# bolid-outputs.net
KiCad netlist of a schematic drawn in Altium Designer
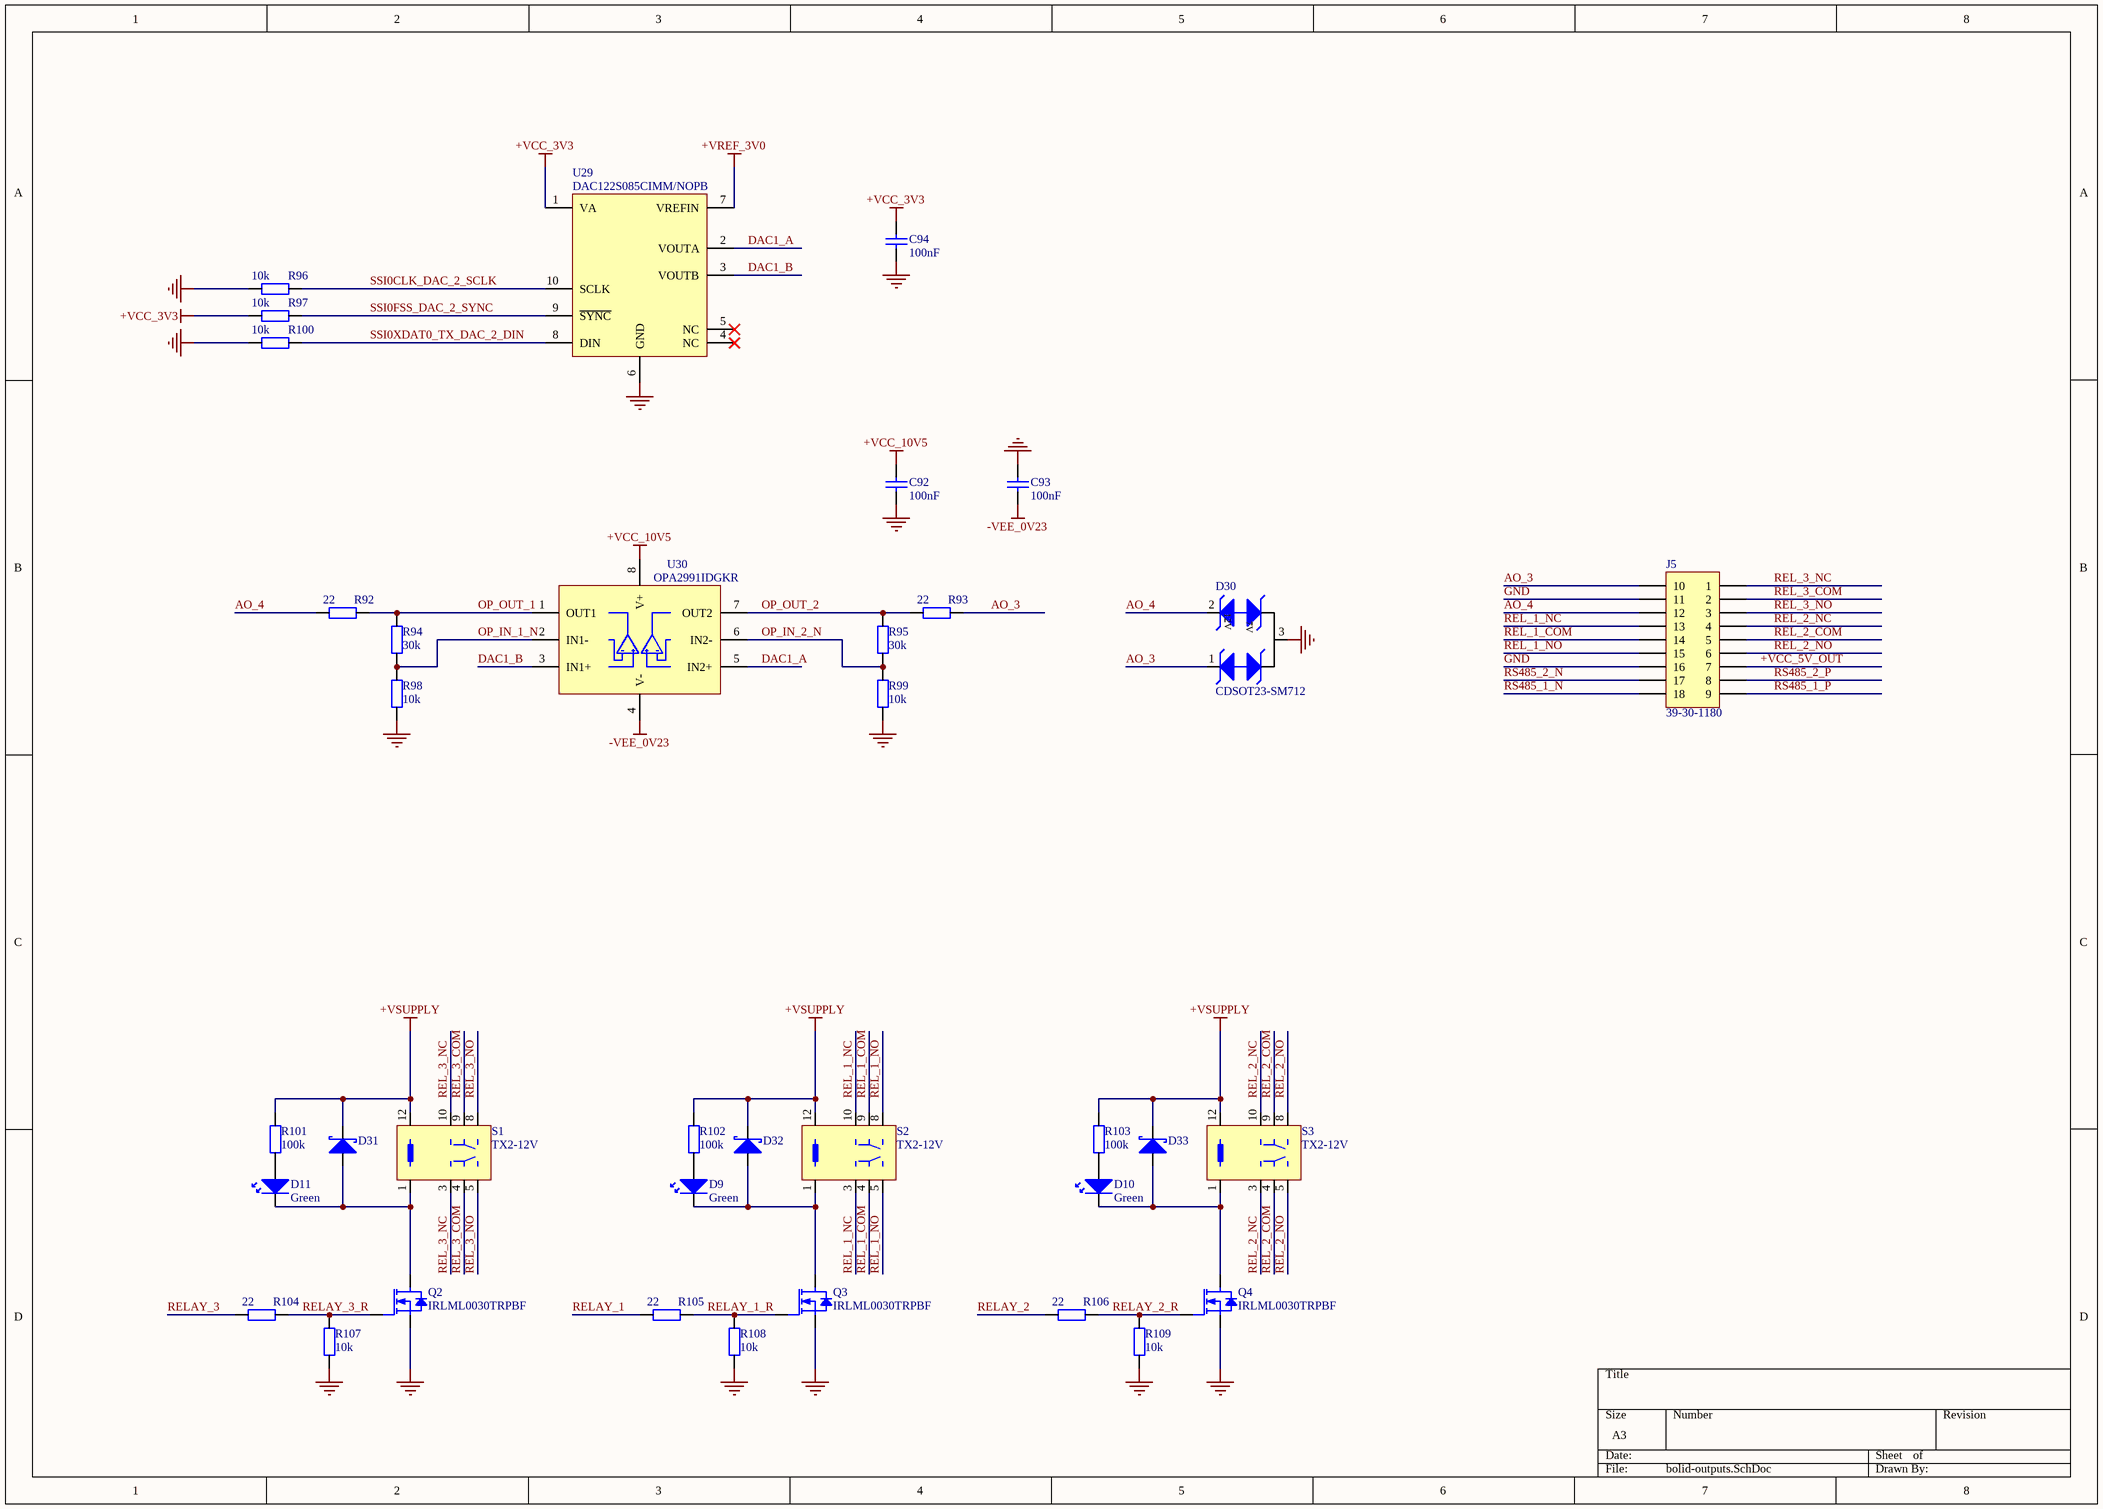
[diagram p0: bolid-outputs.SchDoc]

(export (version "E")
  (design (tool "Eeschema 10.0.6"))
  (components
    (comp (ref "C92")
      (value "GRM155R71H104KE14D")
      (footprint "C0402-CAPC100X50X55L22 - Tayio Yuden TDK")
      (description "MLCC 0402 (1005) 100nF 10% 50V X7R")
      (fields
        (field (name "MANUFACTURER") "Murata Electronics")
        (field (name "TOLERANCE") "10 %")
        (field (name "VALUE DISPLAYED") "100nF")
      )
      (libsource (lib "capacitors2") (part "GRM155R71H104KE14D"))
    )
    (comp (ref "C93")
      (value "GRM155R71H104KE14D")
      (footprint "C0402-CAPC100X50X55L22 - Tayio Yuden TDK")
      (description "MLCC 0402 (1005) 100nF 10% 50V X7R")
      (fields
        (field (name "MANUFACTURER") "Murata Electronics")
        (field (name "TOLERANCE") "10 %")
        (field (name "VALUE DISPLAYED") "100nF")
      )
      (libsource (lib "capacitors2") (part "GRM155R71H104KE14D"))
    )
    (comp (ref "C94")
      (value "GRM155R71H104KE14D")
      (footprint "C0402-CAPC100X50X55L22 - Tayio Yuden TDK")
      (description "MLCC 0402 (1005) 100nF 10% 50V X7R")
      (fields
        (field (name "MANUFACTURER") "Murata Electronics")
        (field (name "TOLERANCE") "10 %")
        (field (name "VALUE DISPLAYED") "100nF")
      )
      (libsource (lib "capacitors2") (part "GRM155R71H104KE14D"))
    )
    (comp (ref "D9")
      (value "150060GS75000")
      (footprint "D0603 DIONC166X84X36L42N Littelfuse")
      (description "LED 0603 (1608) Green")
      (fields (field (name "MANUFACTURER") "Wurth Elektronik") (field (name "ILLUMINATION COLOR") "Green"))
      (libsource (lib "semiconductors2") (part "150060GS75000"))
    )
    (comp (ref "D10")
      (value "150060GS75000")
      (footprint "D0603 DIONC166X84X36L42N Littelfuse")
      (description "LED 0603 (1608) Green")
      (fields (field (name "MANUFACTURER") "Wurth Elektronik") (field (name "ILLUMINATION COLOR") "Green"))
      (libsource (lib "semiconductors2") (part "150060GS75000"))
    )
    (comp (ref "D11")
      (value "150060GS75000")
      (footprint "D0603 DIONC166X84X36L42N Littelfuse")
      (description "LED 0603 (1608) Green")
      (fields (field (name "MANUFACTURER") "Wurth Elektronik") (field (name "ILLUMINATION COLOR") "Green"))
      (libsource (lib "semiconductors2") (part "150060GS75000"))
    )
    (comp (ref "D30")
      (value "CDSOT23-SM712")
      (footprint "Bourns SOT-23-3L SOT23-3P95_229X117L49X40N")
      (description "TVS DIODE 7VWM/12VWM SOT23")
      (fields (field (name "MANUFACTURER") "Bourns"))
      (libsource (lib "semiconductors2") (part "CDSOT23-SM712"))
    )
    (comp (ref "D31")
      (value "MBR0530T3G")
      (footprint "SOD-123-2L SOD375X160X128L32X60N - Fairchild")
      (description "ON Semi MBR0530T3G; SMT Schottky Diode; 30V 500mA; 2-Pin SOD-123")
      (fields (field (name "MANUFACTURER") "ON Semiconductor"))
      (libsource (lib "semiconductors2") (part "MBR0530T3G"))
    )
    (comp (ref "D32")
      (value "MBR0530T3G")
      (footprint "SOD-123-2L SOD375X160X128L32X60N - Fairchild")
      (description "ON Semi MBR0530T3G; SMT Schottky Diode; 30V 500mA; 2-Pin SOD-123")
      (fields (field (name "MANUFACTURER") "ON Semiconductor"))
      (libsource (lib "semiconductors2") (part "MBR0530T3G"))
    )
    (comp (ref "D33")
      (value "MBR0530T3G")
      (footprint "SOD-123-2L SOD375X160X128L32X60N - Fairchild")
      (description "ON Semi MBR0530T3G; SMT Schottky Diode; 30V 500mA; 2-Pin SOD-123")
      (fields (field (name "MANUFACTURER") "ON Semiconductor"))
      (libsource (lib "semiconductors2") (part "MBR0530T3G"))
    )
    (comp (ref "J5")
      (value "39-30-1180")
      (footprint "MOLEX Mini-Fit Jr 039301180 2x9 PEG")
      (fields (field (name "MANUFACTURER") "Molex"))
      (libsource (lib "connectors2") (part "039301180"))
    )
    (comp (ref "Q2")
      (value "IRLML0030TRPBF")
      (footprint "SOT23-3P95_237X112L50X40N - Infineon Micro3")
      (description "MOSFET MOSFT 30V 5.2A 28mOhm 3.6nC Qg")
      (fields (field (name "MANUFACTURER") "Infineon Technologies"))
      (libsource (lib "semiconductors2") (part "IRLML0030TRPBF"))
    )
    (comp (ref "Q3")
      (value "IRLML0030TRPBF")
      (footprint "SOT23-3P95_237X112L50X40N - Infineon Micro3")
      (description "MOSFET MOSFT 30V 5.2A 28mOhm 3.6nC Qg")
      (fields (field (name "MANUFACTURER") "Infineon Technologies"))
      (libsource (lib "semiconductors2") (part "IRLML0030TRPBF"))
    )
    (comp (ref "Q4")
      (value "IRLML0030TRPBF")
      (footprint "SOT23-3P95_237X112L50X40N - Infineon Micro3")
      (description "MOSFET MOSFT 30V 5.2A 28mOhm 3.6nC Qg")
      (fields (field (name "MANUFACTURER") "Infineon Technologies"))
      (libsource (lib "semiconductors2") (part "IRLML0030TRPBF"))
    )
    (comp (ref "R92")
      (value "22")
      (footprint "R0402-RESC100X50X40L22N")
      (description "RES 0402 (1005) 22.0 ohm 1% 0.0625W 50V Thick Film")
      (fields
        (field (name "MANUFACTURER") "Yageo")
        (field (name "MANUFACTURER PART NUMBER") "RC0402FR-1322RL")
      )
      (libsource (lib "resistors2") (part "RC0402FR-1322RL"))
    )
    (comp (ref "R93")
      (value "22")
      (footprint "R0402-RESC100X50X40L22N")
      (description "RES 0402 (1005) 22.0 ohm 1% 0.0625W 50V Thick Film")
      (fields
        (field (name "MANUFACTURER") "Yageo")
        (field (name "MANUFACTURER PART NUMBER") "RC0402FR-1322RL")
      )
      (libsource (lib "resistors2") (part "RC0402FR-1322RL"))
    )
    (comp (ref "R94")
      (value "30k")
      (footprint "R0402-RESC100X50X40L22N")
      (description "RES 0402 (1005) 30.0k 1% 0.0625W 50V Thick Film")
      (fields
        (field (name "MANUFACTURER") "Yageo")
        (field (name "MANUFACTURER PART NUMBER") "RC0402FR-1330KL")
      )
      (libsource (lib "") (part "RC0402FR-1330KL_1"))
    )
    (comp (ref "R95")
      (value "30k")
      (footprint "R0402-RESC100X50X40L22N")
      (description "RES 0402 (1005) 30.0k 1% 0.0625W 50V Thick Film")
      (fields
        (field (name "MANUFACTURER") "Yageo")
        (field (name "MANUFACTURER PART NUMBER") "RC0402FR-1330KL")
      )
      (libsource (lib "resistors2") (part "RC0402FR-1330KL"))
    )
    (comp (ref "R96")
      (value "10k")
      (footprint "R0402-RESC100X50X40L22N")
      (description "RES 0402 (1005) 10.0k 1% 0.0625W 50V Thick Film")
      (fields
        (field (name "MANUFACTURER") "Yageo")
        (field (name "MANUFACTURER PART NUMBER") "RC0402FR-0710KL")
      )
      (libsource (lib "") (part "RC0402FR-0710KL_1"))
    )
    (comp (ref "R97")
      (value "10k")
      (footprint "R0402-RESC100X50X40L22N")
      (description "RES 0402 (1005) 10.0k 1% 0.0625W 50V Thick Film")
      (fields
        (field (name "MANUFACTURER") "Yageo")
        (field (name "MANUFACTURER PART NUMBER") "RC0402FR-0710KL")
      )
      (libsource (lib "") (part "RC0402FR-0710KL_1"))
    )
    (comp (ref "R98")
      (value "10k")
      (footprint "R0402-RESC100X50X40L22N")
      (description "RES 0402 (1005) 10.0k 1% 0.0625W 50V Thick Film")
      (fields
        (field (name "MANUFACTURER") "Yageo")
        (field (name "MANUFACTURER PART NUMBER") "RC0402FR-0710KL")
      )
      (libsource (lib "") (part "RC0402FR-0710KL_2"))
    )
    (comp (ref "R99")
      (value "10k")
      (footprint "R0402-RESC100X50X40L22N")
      (description "RES 0402 (1005) 10.0k 1% 0.0625W 50V Thick Film")
      (fields
        (field (name "MANUFACTURER") "Yageo")
        (field (name "MANUFACTURER PART NUMBER") "RC0402FR-0710KL")
      )
      (libsource (lib "resistors2") (part "RC0402FR-0710KL"))
    )
    (comp (ref "R100")
      (value "10k")
      (footprint "R0402-RESC100X50X40L22N")
      (description "RES 0402 (1005) 10.0k 1% 0.0625W 50V Thick Film")
      (fields
        (field (name "MANUFACTURER") "Yageo")
        (field (name "MANUFACTURER PART NUMBER") "RC0402FR-0710KL")
      )
      (libsource (lib "") (part "RC0402FR-0710KL_1"))
    )
    (comp (ref "R101")
      (value "100k")
      (footprint "R0402-RESC100X50X40L22N")
      (description "RES 0402 (1005) 100.0k 1% 0.0625W 50V Thick Film")
      (fields
        (field (name "MANUFACTURER") "Yageo")
        (field (name "MANUFACTURER PART NUMBER") "RC0402FR-07100KL")
      )
      (libsource (lib "resistors2") (part "RC0402FR-07100KL"))
    )
    (comp (ref "R102")
      (value "100k")
      (footprint "R0402-RESC100X50X40L22N")
      (description "RES 0402 (1005) 100.0k 1% 0.0625W 50V Thick Film")
      (fields
        (field (name "MANUFACTURER") "Yageo")
        (field (name "MANUFACTURER PART NUMBER") "RC0402FR-07100KL")
      )
      (libsource (lib "resistors2") (part "RC0402FR-07100KL"))
    )
    (comp (ref "R103")
      (value "100k")
      (footprint "R0402-RESC100X50X40L22N")
      (description "RES 0402 (1005) 100.0k 1% 0.0625W 50V Thick Film")
      (fields
        (field (name "MANUFACTURER") "Yageo")
        (field (name "MANUFACTURER PART NUMBER") "RC0402FR-07100KL")
      )
      (libsource (lib "resistors2") (part "RC0402FR-07100KL"))
    )
    (comp (ref "R104")
      (value "22")
      (footprint "R0402-RESC100X50X40L22N")
      (description "RES 0402 (1005) 22.0 ohm 1% 0.0625W 50V Thick Film")
      (fields
        (field (name "MANUFACTURER") "Yageo")
        (field (name "MANUFACTURER PART NUMBER") "RC0402FR-1322RL")
      )
      (libsource (lib "resistors2") (part "RC0402FR-1322RL"))
    )
    (comp (ref "R105")
      (value "22")
      (footprint "R0402-RESC100X50X40L22N")
      (description "RES 0402 (1005) 22.0 ohm 1% 0.0625W 50V Thick Film")
      (fields
        (field (name "MANUFACTURER") "Yageo")
        (field (name "MANUFACTURER PART NUMBER") "RC0402FR-1322RL")
      )
      (libsource (lib "resistors2") (part "RC0402FR-1322RL"))
    )
    (comp (ref "R106")
      (value "22")
      (footprint "R0402-RESC100X50X40L22N")
      (description "RES 0402 (1005) 22.0 ohm 1% 0.0625W 50V Thick Film")
      (fields
        (field (name "MANUFACTURER") "Yageo")
        (field (name "MANUFACTURER PART NUMBER") "RC0402FR-1322RL")
      )
      (libsource (lib "resistors2") (part "RC0402FR-1322RL"))
    )
    (comp (ref "R107")
      (value "10k")
      (footprint "R0402-RESC100X50X40L22N")
      (description "RES 0402 (1005) 10.0k 1% 0.0625W 50V Thick Film")
      (fields
        (field (name "MANUFACTURER") "Yageo")
        (field (name "MANUFACTURER PART NUMBER") "RC0402FR-0710KL")
      )
      (libsource (lib "") (part "RC0402FR-0710KL_2"))
    )
    (comp (ref "R108")
      (value "10k")
      (footprint "R0402-RESC100X50X40L22N")
      (description "RES 0402 (1005) 10.0k 1% 0.0625W 50V Thick Film")
      (fields
        (field (name "MANUFACTURER") "Yageo")
        (field (name "MANUFACTURER PART NUMBER") "RC0402FR-0710KL")
      )
      (libsource (lib "") (part "RC0402FR-0710KL_2"))
    )
    (comp (ref "R109")
      (value "10k")
      (footprint "R0402-RESC100X50X40L22N")
      (description "RES 0402 (1005) 10.0k 1% 0.0625W 50V Thick Film")
      (fields
        (field (name "MANUFACTURER") "Yageo")
        (field (name "MANUFACTURER PART NUMBER") "RC0402FR-0710KL")
      )
      (libsource (lib "") (part "RC0402FR-0710KL_2"))
    )
    (comp (ref "S1")
      (value "TX2-12V")
      (footprint "NAiS_TX2")
      (description "Electromechanical Relay 12VDC 1.028KOhm 2A DPDT (15x7.4x8.2)mm THT General Purpose Relay")
      (fields (field (name "MANUFACTURER") "Panasonic"))
      (libsource (lib "electromechanical2") (part "TX2-12V"))
    )
    (comp (ref "S2")
      (value "TX2-12V")
      (footprint "NAiS_TX2")
      (description "Electromechanical Relay 12VDC 1.028KOhm 2A DPDT (15x7.4x8.2)mm THT General Purpose Relay")
      (fields (field (name "MANUFACTURER") "Panasonic"))
      (libsource (lib "electromechanical2") (part "TX2-12V"))
    )
    (comp (ref "S3")
      (value "TX2-12V")
      (footprint "NAiS_TX2")
      (description "Electromechanical Relay 12VDC 1.028KOhm 2A DPDT (15x7.4x8.2)mm THT General Purpose Relay")
      (fields (field (name "MANUFACTURER") "Panasonic"))
      (libsource (lib "electromechanical2") (part "TX2-12V"))
    )
    (comp (ref "U29")
      (value "DAC122S085CIMM/NOPB")
      (footprint "TI VSSOP10 DGS0010A TSSOP50P490X110-10N")
      (description "12-Bit Micro Power DUAL Digital-to-Analog Converter with ail-to- ail Output 10-VSSOP -40 to 105")
      (fields (field (name "MANUFACTURER") "TI National Semiconductor"))
      (libsource (lib "ics2") (part "DAC122S085CIMM/NOPB"))
    )
    (comp (ref "U30")
      (value "OPA2991IDGKR")
      (footprint "TI VSSOP8 DGK0008A TSOP65P490X110-8N")
      (fields (field (name "MANUFACTURER") "Texas Instruments"))
      (libsource (lib "ics2") (part "OPA2991IDGKR"))
    )
  )
  (nets
    (net (code "1") (name "+VCC_3V3") (class "Default")
      (node (ref "C94") (pin "2") (pinfunction "2_2") (pintype "passive"))
      (node (ref "R97") (pin "2") (pinfunction "2_2") (pintype "passive"))
      (node (ref "U29") (pin "1") (pinfunction "VA_1") (pintype "passive"))
    )
    (net (code "2") (name "+VCC_10V5") (class "Default")
      (node (ref "C92") (pin "2") (pinfunction "2_2") (pintype "passive"))
      (node (ref "U30") (pin "8") (pinfunction "V+_8") (pintype "passive"))
    )
    (net (code "3") (name "+VREF_3V0") (class "Default")
      (node (ref "U29") (pin "7") (pinfunction "VREFIN_7") (pintype "passive"))
    )
    (net (code "4") (name "+VSUPPLY") (class "Default")
      (node (ref "D31") (pin "1") (pinfunction "K_1") (pintype "passive"))
      (node (ref "D32") (pin "1") (pinfunction "K_1") (pintype "passive"))
      (node (ref "D33") (pin "1") (pinfunction "K_1") (pintype "passive"))
      (node (ref "R101") (pin "2") (pinfunction "2_2") (pintype "passive"))
      (node (ref "R102") (pin "2") (pinfunction "2_2") (pintype "passive"))
      (node (ref "R103") (pin "2") (pinfunction "2_2") (pintype "passive"))
      (node (ref "S1") (pin "12") (pinfunction "12_12") (pintype "passive"))
      (node (ref "S2") (pin "12") (pinfunction "12_12") (pintype "passive"))
      (node (ref "S3") (pin "12") (pinfunction "12_12") (pintype "passive"))
    )
    (net (code "5") (name "-VEE_0V23") (class "Default")
      (node (ref "C93") (pin "1") (pinfunction "1_1") (pintype "passive"))
      (node (ref "U30") (pin "4") (pinfunction "V-_4") (pintype "passive"))
    )
    (net (code "6") (name "/+VCC_5V_OUT") (class "Default")
      (node (ref "J5") (pin "7") (pinfunction "7_7") (pintype "passive"))
    )
    (net (code "7") (name "/AO_3") (class "Default")
      (node (ref "D30") (pin "1") (pinfunction "1_1") (pintype "passive"))
      (node (ref "J5") (pin "10") (pinfunction "10_10") (pintype "passive"))
      (node (ref "R93") (pin "2") (pinfunction "2_2") (pintype "passive"))
    )
    (net (code "8") (name "/AO_4") (class "Default")
      (node (ref "D30") (pin "2") (pinfunction "2_2") (pintype "passive"))
      (node (ref "J5") (pin "12") (pinfunction "12_12") (pintype "passive"))
      (node (ref "R92") (pin "1") (pinfunction "1_1") (pintype "passive"))
    )
    (net (code "9") (name "/DAC1_A") (class "Default")
      (node (ref "U29") (pin "2") (pinfunction "VOUTA_2") (pintype "passive"))
      (node (ref "U30") (pin "5") (pinfunction "IN2+_5") (pintype "passive"))
    )
    (net (code "10") (name "/DAC1_B") (class "Default")
      (node (ref "U29") (pin "3") (pinfunction "VOUTB_3") (pintype "passive"))
      (node (ref "U30") (pin "3") (pinfunction "IN1+_3") (pintype "passive"))
    )
    (net (code "11") (name "/OP_IN_1_N") (class "Default")
      (node (ref "R94") (pin "1") (pinfunction "1_1") (pintype "passive"))
      (node (ref "R98") (pin "2") (pinfunction "2_2") (pintype "passive"))
      (node (ref "U30") (pin "2") (pinfunction "IN1-_2") (pintype "passive"))
    )
    (net (code "12") (name "/OP_IN_2_N") (class "Default")
      (node (ref "R95") (pin "1") (pinfunction "1_1") (pintype "passive"))
      (node (ref "R99") (pin "2") (pinfunction "2_2") (pintype "passive"))
      (node (ref "U30") (pin "6") (pinfunction "IN2-_6") (pintype "passive"))
    )
    (net (code "13") (name "/OP_OUT_1") (class "Default")
      (node (ref "R92") (pin "2") (pinfunction "2_2") (pintype "passive"))
      (node (ref "R94") (pin "2") (pinfunction "2_2") (pintype "passive"))
      (node (ref "U30") (pin "1") (pinfunction "OUT1_1") (pintype "passive"))
    )
    (net (code "14") (name "/OP_OUT_2") (class "Default")
      (node (ref "R93") (pin "1") (pinfunction "1_1") (pintype "passive"))
      (node (ref "R95") (pin "2") (pinfunction "2_2") (pintype "passive"))
      (node (ref "U30") (pin "7") (pinfunction "OUT2_7") (pintype "passive"))
    )
    (net (code "15") (name "/RELAY_1") (class "Default")
      (node (ref "R105") (pin "1") (pinfunction "1_1") (pintype "passive"))
    )
    (net (code "16") (name "/RELAY_1_R") (class "Default")
      (node (ref "Q3") (pin "1") (pinfunction "G_1") (pintype "passive"))
      (node (ref "R105") (pin "2") (pinfunction "2_2") (pintype "passive"))
      (node (ref "R108") (pin "2") (pinfunction "2_2") (pintype "passive"))
    )
    (net (code "17") (name "/RELAY_2") (class "Default")
      (node (ref "R106") (pin "1") (pinfunction "1_1") (pintype "passive"))
    )
    (net (code "18") (name "/RELAY_2_R") (class "Default")
      (node (ref "Q4") (pin "1") (pinfunction "G_1") (pintype "passive"))
      (node (ref "R106") (pin "2") (pinfunction "2_2") (pintype "passive"))
      (node (ref "R109") (pin "2") (pinfunction "2_2") (pintype "passive"))
    )
    (net (code "19") (name "/RELAY_3") (class "Default")
      (node (ref "R104") (pin "1") (pinfunction "1_1") (pintype "passive"))
    )
    (net (code "20") (name "/RELAY_3_R") (class "Default")
      (node (ref "Q2") (pin "1") (pinfunction "G_1") (pintype "passive"))
      (node (ref "R104") (pin "2") (pinfunction "2_2") (pintype "passive"))
      (node (ref "R107") (pin "2") (pinfunction "2_2") (pintype "passive"))
    )
    (net (code "21") (name "/REL_1_COM") (class "Default")
      (node (ref "J5") (pin "14") (pinfunction "14_14") (pintype "passive"))
      (node (ref "S2") (pin "4") (pinfunction "4_4") (pintype "passive"))
      (node (ref "S2") (pin "9") (pinfunction "9_9") (pintype "passive"))
    )
    (net (code "22") (name "/REL_1_NC") (class "Default")
      (node (ref "J5") (pin "13") (pinfunction "13_13") (pintype "passive"))
      (node (ref "S2") (pin "10") (pinfunction "10_10") (pintype "passive"))
      (node (ref "S2") (pin "3") (pinfunction "3_3") (pintype "passive"))
    )
    (net (code "23") (name "/REL_1_NO") (class "Default")
      (node (ref "J5") (pin "15") (pinfunction "15_15") (pintype "passive"))
      (node (ref "S2") (pin "5") (pinfunction "5_5") (pintype "passive"))
      (node (ref "S2") (pin "8") (pinfunction "8_8") (pintype "passive"))
    )
    (net (code "24") (name "/REL_2_COM") (class "Default")
      (node (ref "J5") (pin "5") (pinfunction "5_5") (pintype "passive"))
      (node (ref "S3") (pin "4") (pinfunction "4_4") (pintype "passive"))
      (node (ref "S3") (pin "9") (pinfunction "9_9") (pintype "passive"))
    )
    (net (code "25") (name "/REL_2_NC") (class "Default")
      (node (ref "J5") (pin "4") (pinfunction "4_4") (pintype "passive"))
      (node (ref "S3") (pin "10") (pinfunction "10_10") (pintype "passive"))
      (node (ref "S3") (pin "3") (pinfunction "3_3") (pintype "passive"))
    )
    (net (code "26") (name "/REL_2_NO") (class "Default")
      (node (ref "J5") (pin "6") (pinfunction "6_6") (pintype "passive"))
      (node (ref "S3") (pin "5") (pinfunction "5_5") (pintype "passive"))
      (node (ref "S3") (pin "8") (pinfunction "8_8") (pintype "passive"))
    )
    (net (code "27") (name "/REL_3_COM") (class "Default")
      (node (ref "J5") (pin "2") (pinfunction "2_2") (pintype "passive"))
      (node (ref "S1") (pin "4") (pinfunction "4_4") (pintype "passive"))
      (node (ref "S1") (pin "9") (pinfunction "9_9") (pintype "passive"))
    )
    (net (code "28") (name "/REL_3_NC") (class "Default")
      (node (ref "J5") (pin "1") (pinfunction "1_1") (pintype "passive"))
      (node (ref "S1") (pin "10") (pinfunction "10_10") (pintype "passive"))
      (node (ref "S1") (pin "3") (pinfunction "3_3") (pintype "passive"))
    )
    (net (code "29") (name "/REL_3_NO") (class "Default")
      (node (ref "J5") (pin "3") (pinfunction "3_3") (pintype "passive"))
      (node (ref "S1") (pin "5") (pinfunction "5_5") (pintype "passive"))
      (node (ref "S1") (pin "8") (pinfunction "8_8") (pintype "passive"))
    )
    (net (code "30") (name "/RS485_1_N") (class "Default")
      (node (ref "J5") (pin "18") (pinfunction "18_18") (pintype "passive"))
    )
    (net (code "31") (name "/RS485_1_P") (class "Default")
      (node (ref "J5") (pin "9") (pinfunction "9_9") (pintype "passive"))
    )
    (net (code "32") (name "/RS485_2_N") (class "Default")
      (node (ref "J5") (pin "17") (pinfunction "17_17") (pintype "passive"))
    )
    (net (code "33") (name "/RS485_2_P") (class "Default")
      (node (ref "J5") (pin "8") (pinfunction "8_8") (pintype "passive"))
    )
    (net (code "34") (name "/SSI0CLK_DAC_2_SCLK") (class "Default")
      (node (ref "R96") (pin "1") (pinfunction "1_1") (pintype "passive"))
      (node (ref "U29") (pin "10") (pinfunction "SCLK_10") (pintype "passive"))
    )
    (net (code "35") (name "/SSI0FSS_DAC_2_SYNC") (class "Default")
      (node (ref "R97") (pin "1") (pinfunction "1_1") (pintype "passive"))
      (node (ref "U29") (pin "9") (pinfunction "~{SYNC}_9") (pintype "passive"))
    )
    (net (code "36") (name "/SSI0XDAT0_TX_DAC_2_DIN") (class "Default")
      (node (ref "R100") (pin "1") (pinfunction "1_1") (pintype "passive"))
      (node (ref "U29") (pin "8") (pinfunction "DIN_8") (pintype "passive"))
    )
    (net (code "37") (name "GND") (class "Default")
      (node (ref "C92") (pin "1") (pinfunction "1_1") (pintype "passive"))
      (node (ref "C93") (pin "2") (pinfunction "2_2") (pintype "passive"))
      (node (ref "C94") (pin "1") (pinfunction "1_1") (pintype "passive"))
      (node (ref "D30") (pin "3") (pinfunction "3_3") (pintype "passive"))
      (node (ref "J5") (pin "11") (pinfunction "11_11") (pintype "passive"))
      (node (ref "J5") (pin "16") (pinfunction "16_16") (pintype "passive"))
      (node (ref "Q2") (pin "2") (pinfunction "S_2") (pintype "passive"))
      (node (ref "Q3") (pin "2") (pinfunction "S_2") (pintype "passive"))
      (node (ref "Q4") (pin "2") (pinfunction "S_2") (pintype "passive"))
      (node (ref "R100") (pin "2") (pinfunction "2_2") (pintype "passive"))
      (node (ref "R107") (pin "1") (pinfunction "1_1") (pintype "passive"))
      (node (ref "R108") (pin "1") (pinfunction "1_1") (pintype "passive"))
      (node (ref "R109") (pin "1") (pinfunction "1_1") (pintype "passive"))
      (node (ref "R96") (pin "2") (pinfunction "2_2") (pintype "passive"))
      (node (ref "R98") (pin "1") (pinfunction "1_1") (pintype "passive"))
      (node (ref "R99") (pin "1") (pinfunction "1_1") (pintype "passive"))
      (node (ref "U29") (pin "6") (pinfunction "GND_6") (pintype "passive"))
    )
    (net (code "38") (name "Net-(D9-A)") (class "Default")
      (node (ref "D9") (pin "2") (pinfunction "A_2") (pintype "passive"))
      (node (ref "R102") (pin "1") (pinfunction "1_1") (pintype "passive"))
    )
    (net (code "39") (name "Net-(D10-A)") (class "Default")
      (node (ref "D10") (pin "2") (pinfunction "A_2") (pintype "passive"))
      (node (ref "R103") (pin "1") (pinfunction "1_1") (pintype "passive"))
    )
    (net (code "40") (name "Net-(D10-K)") (class "Default")
      (node (ref "D10") (pin "1") (pinfunction "K_1") (pintype "passive"))
      (node (ref "D33") (pin "2") (pinfunction "A_2") (pintype "passive"))
      (node (ref "Q4") (pin "3") (pinfunction "D_3") (pintype "passive"))
      (node (ref "S3") (pin "1") (pinfunction "1_1") (pintype "passive"))
    )
    (net (code "41") (name "Net-(D11-A)") (class "Default")
      (node (ref "D11") (pin "2") (pinfunction "A_2") (pintype "passive"))
      (node (ref "R101") (pin "1") (pinfunction "1_1") (pintype "passive"))
    )
    (net (code "42") (name "Net-(D11-K)") (class "Default")
      (node (ref "D11") (pin "1") (pinfunction "K_1") (pintype "passive"))
      (node (ref "D31") (pin "2") (pinfunction "A_2") (pintype "passive"))
      (node (ref "Q2") (pin "3") (pinfunction "D_3") (pintype "passive"))
      (node (ref "S1") (pin "1") (pinfunction "1_1") (pintype "passive"))
    )
    (net (code "43") (name "Net-(D32-A)") (class "Default")
      (node (ref "D32") (pin "2") (pinfunction "A_2") (pintype "passive"))
      (node (ref "D9") (pin "1") (pinfunction "K_1") (pintype "passive"))
      (node (ref "Q3") (pin "3") (pinfunction "D_3") (pintype "passive"))
      (node (ref "S2") (pin "1") (pinfunction "1_1") (pintype "passive"))
    )
    (net (code "44") (name "unconnected-(U29-NC-Pad4)") (class "Default")
      (node (ref "U29") (pin "4") (pinfunction "NC_4") (pintype "passive+no_connect"))
    )
    (net (code "45") (name "unconnected-(U29-NC-Pad5)") (class "Default")
      (node (ref "U29") (pin "5") (pinfunction "NC_5") (pintype "passive+no_connect"))
    )
  )
)
